# ddr2_memory.net
KiCad netlist of a schematic drawn in Altium Designer
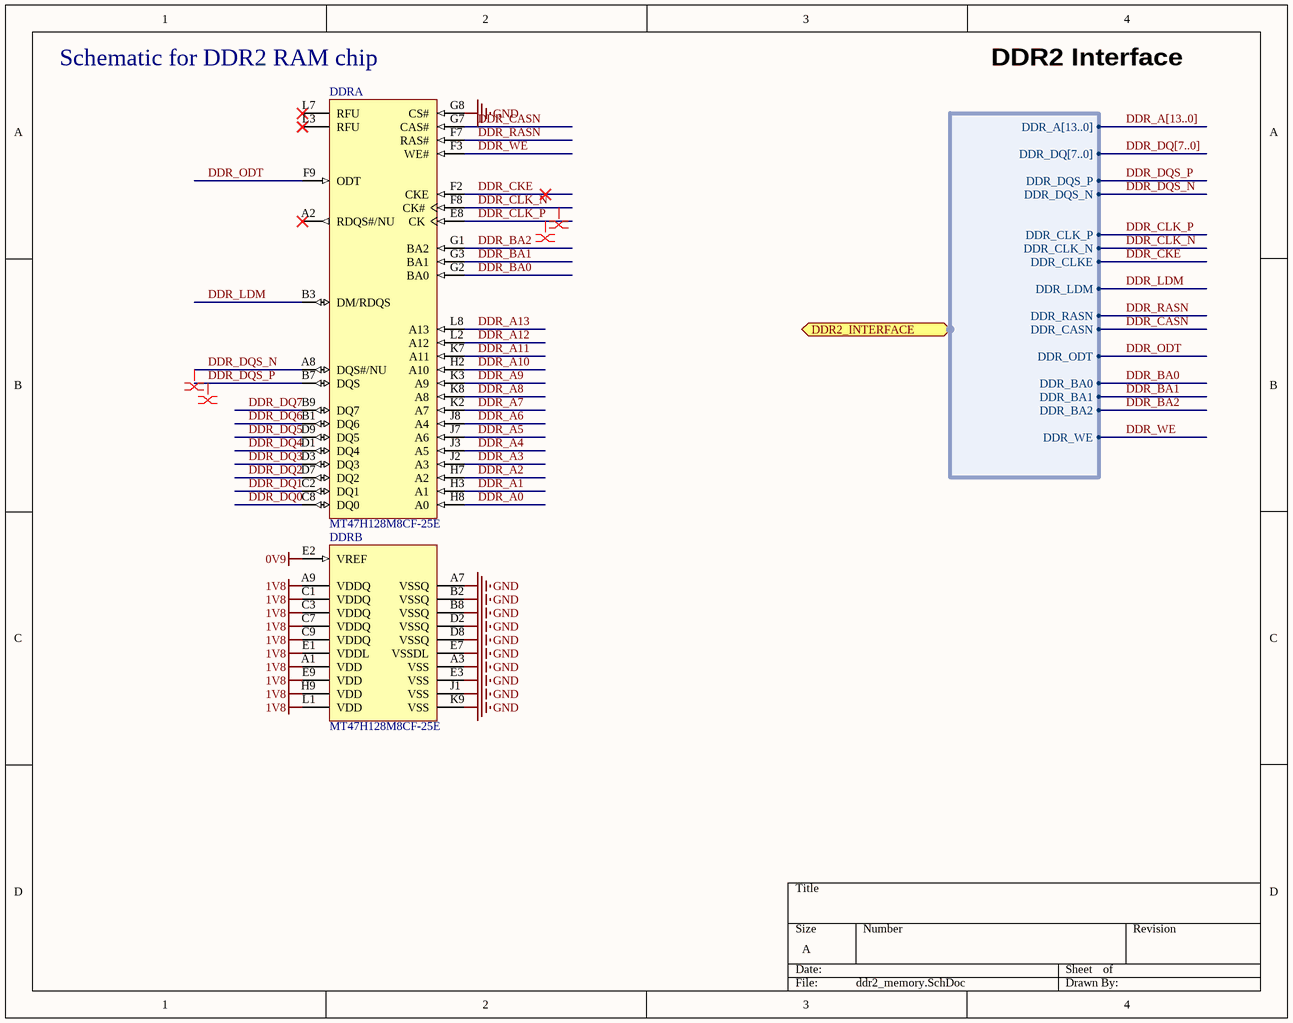
[diagram p0: ddr2_memory.SchDoc]

(export (version "E")
  (design (tool "Eeschema 10.0.6"))
  (components
    (comp (ref "DDR")
      (value "MT47H128M8CF-25E")
      (footprint "MICT-CF-60")
      (description "1Gb DDR2-800 SDRAM, 128Mb x 8, 2.5ns, 1.8V, 0 to 85 degC, 60-Ball FBGA, Pb-Free")
      (fields (field (name "VOLTAGE") "1.8V ") (field (name "MANUFACTURER") "Micron"))
      (libsource (lib "Altium Content Vault") (part "MICT-MT47H128M8CF-60"))
    )
  )
  (nets
    (net (code "3") (name "/DDR_A0") (class "Default")
      (node (ref "DDR") (pin "H8") (pinfunction "A0_H8") (pintype "input"))
    )
    (net (code "4") (name "/DDR_A1") (class "Default")
      (node (ref "DDR") (pin "H3") (pinfunction "A1_H3") (pintype "input"))
    )
    (net (code "5") (name "/DDR_A2") (class "Default")
      (node (ref "DDR") (pin "H7") (pinfunction "A2_H7") (pintype "input"))
    )
    (net (code "6") (name "/DDR_A3") (class "Default")
      (node (ref "DDR") (pin "J2") (pinfunction "A3_J2") (pintype "input"))
    )
    (net (code "7") (name "/DDR_A4") (class "Default")
      (node (ref "DDR") (pin "J3") (pinfunction "A5_J3") (pintype "input"))
    )
    (net (code "8") (name "/DDR_A5") (class "Default")
      (node (ref "DDR") (pin "J7") (pinfunction "A6_J7") (pintype "input"))
    )
    (net (code "9") (name "/DDR_A6") (class "Default")
      (node (ref "DDR") (pin "J8") (pinfunction "A4_J8") (pintype "input"))
    )
    (net (code "10") (name "/DDR_A7") (class "Default")
      (node (ref "DDR") (pin "K2") (pinfunction "A7_K2") (pintype "input"))
    )
    (net (code "11") (name "/DDR_A8") (class "Default")
      (node (ref "DDR") (pin "K8") (pinfunction "A8_K8") (pintype "input"))
    )
    (net (code "12") (name "/DDR_A9") (class "Default")
      (node (ref "DDR") (pin "K3") (pinfunction "A9_K3") (pintype "input"))
    )
    (net (code "13") (name "/DDR_A10") (class "Default")
      (node (ref "DDR") (pin "H2") (pinfunction "A10_H2") (pintype "input"))
    )
    (net (code "14") (name "/DDR_A11") (class "Default")
      (node (ref "DDR") (pin "K7") (pinfunction "A11_K7") (pintype "input"))
    )
    (net (code "15") (name "/DDR_A12") (class "Default")
      (node (ref "DDR") (pin "L2") (pinfunction "A12_L2") (pintype "input"))
    )
    (net (code "16") (name "/DDR_A13") (class "Default")
      (node (ref "DDR") (pin "L8") (pinfunction "A13_L8") (pintype "input"))
    )
    (net (code "18") (name "/DDR_BA0") (class "Default")
      (node (ref "DDR") (pin "G2") (pinfunction "BA0_G2") (pintype "input"))
    )
    (net (code "19") (name "/DDR_BA1") (class "Default")
      (node (ref "DDR") (pin "G3") (pinfunction "BA1_G3") (pintype "input"))
    )
    (net (code "20") (name "/DDR_BA2") (class "Default")
      (node (ref "DDR") (pin "G1") (pinfunction "BA2_G1") (pintype "input"))
    )
    (net (code "21") (name "/DDR_CASN") (class "Default")
      (node (ref "DDR") (pin "G7") (pinfunction "CAS#_G7") (pintype "input"))
    )
    (net (code "22") (name "/DDR_CKE") (class "Default")
      (node (ref "DDR") (pin "F2") (pinfunction "CKE_F2") (pintype "input"))
    )
    (net (code "23") (name "/DDR_CLK_N") (class "Default")
      (node (ref "DDR") (pin "F8") (pinfunction "CK#_F8") (pintype "input"))
    )
    (net (code "24") (name "/DDR_CLK_P") (class "Default")
      (node (ref "DDR") (pin "E8") (pinfunction "CK_E8") (pintype "input"))
    )
    (net (code "25") (name "/DDR_DQ0") (class "Default")
      (node (ref "DDR") (pin "C8") (pinfunction "DQ0_C8") (pintype "bidirectional"))
    )
    (net (code "26") (name "/DDR_DQ1") (class "Default")
      (node (ref "DDR") (pin "C2") (pinfunction "DQ1_C2") (pintype "bidirectional"))
    )
    (net (code "27") (name "/DDR_DQ2") (class "Default")
      (node (ref "DDR") (pin "D7") (pinfunction "DQ2_D7") (pintype "bidirectional"))
    )
    (net (code "28") (name "/DDR_DQ3") (class "Default")
      (node (ref "DDR") (pin "D3") (pinfunction "DQ3_D3") (pintype "bidirectional"))
    )
    (net (code "29") (name "/DDR_DQ4") (class "Default")
      (node (ref "DDR") (pin "D1") (pinfunction "DQ4_D1") (pintype "bidirectional"))
    )
    (net (code "30") (name "/DDR_DQ5") (class "Default")
      (node (ref "DDR") (pin "D9") (pinfunction "DQ5_D9") (pintype "bidirectional"))
    )
    (net (code "31") (name "/DDR_DQ6") (class "Default")
      (node (ref "DDR") (pin "B1") (pinfunction "DQ6_B1") (pintype "bidirectional"))
    )
    (net (code "32") (name "/DDR_DQ7") (class "Default")
      (node (ref "DDR") (pin "B9") (pinfunction "DQ7_B9") (pintype "bidirectional"))
    )
    (net (code "33") (name "/DDR_DQS_N") (class "Default")
      (node (ref "DDR") (pin "A8") (pinfunction "DQS#/NU_A8") (pintype "bidirectional"))
    )
    (net (code "34") (name "/DDR_DQS_P") (class "Default")
      (node (ref "DDR") (pin "B7") (pinfunction "DQS_B7") (pintype "bidirectional"))
    )
    (net (code "35") (name "/DDR_LDM") (class "Default")
      (node (ref "DDR") (pin "B3") (pinfunction "DM/RDQS_B3") (pintype "bidirectional"))
    )
    (net (code "36") (name "/DDR_ODT") (class "Default")
      (node (ref "DDR") (pin "F9") (pinfunction "ODT_F9") (pintype "input"))
    )
    (net (code "37") (name "/DDR_RASN") (class "Default")
      (node (ref "DDR") (pin "F7") (pinfunction "RAS#_F7") (pintype "input"))
    )
    (net (code "38") (name "/DDR_WE") (class "Default")
      (node (ref "DDR") (pin "F3") (pinfunction "WE#_F3") (pintype "input"))
    )
    (net (code "40") (name "0V9") (class "Default")
      (node (ref "DDR") (pin "E2") (pinfunction "VREF_E2") (pintype "input"))
    )
    (net (code "41") (name "1V8") (class "Default")
      (node (ref "DDR") (pin "A1") (pinfunction "VDD_A1") (pintype "power_in"))
      (node (ref "DDR") (pin "A9") (pinfunction "VDDQ_A9") (pintype "power_in"))
      (node (ref "DDR") (pin "C1") (pinfunction "VDDQ_C1") (pintype "power_in"))
      (node (ref "DDR") (pin "C3") (pinfunction "VDDQ_C3") (pintype "power_in"))
      (node (ref "DDR") (pin "C7") (pinfunction "VDDQ_C7") (pintype "power_in"))
      (node (ref "DDR") (pin "C9") (pinfunction "VDDQ_C9") (pintype "power_in"))
      (node (ref "DDR") (pin "E1") (pinfunction "VDDL_E1") (pintype "power_in"))
      (node (ref "DDR") (pin "E9") (pinfunction "VDD_E9") (pintype "power_in"))
      (node (ref "DDR") (pin "H9") (pinfunction "VDD_H9") (pintype "power_in"))
      (node (ref "DDR") (pin "L1") (pinfunction "VDD_L1") (pintype "power_in"))
    )
    (net (code "42") (name "GND") (class "Default")
      (node (ref "DDR") (pin "A3") (pinfunction "VSS_A3") (pintype "power_in"))
      (node (ref "DDR") (pin "A7") (pinfunction "VSSQ_A7") (pintype "power_in"))
      (node (ref "DDR") (pin "B2") (pinfunction "VSSQ_B2") (pintype "power_in"))
      (node (ref "DDR") (pin "B8") (pinfunction "VSSQ_B8") (pintype "power_in"))
      (node (ref "DDR") (pin "D2") (pinfunction "VSSQ_D2") (pintype "power_in"))
      (node (ref "DDR") (pin "D8") (pinfunction "VSSQ_D8") (pintype "power_in"))
      (node (ref "DDR") (pin "E3") (pinfunction "VSS_E3") (pintype "power_in"))
      (node (ref "DDR") (pin "E7") (pinfunction "VSSDL_E7") (pintype "power_in"))
      (node (ref "DDR") (pin "G8") (pinfunction "CS#_G8") (pintype "input"))
      (node (ref "DDR") (pin "J1") (pinfunction "VSS_J1") (pintype "power_in"))
      (node (ref "DDR") (pin "K9") (pinfunction "VSS_K9") (pintype "power_in"))
    )
    (net (code "43") (name "unconnected-(DDRA-RDQS#{slash}NU-PadA2)") (class "Default")
      (node (ref "DDR") (pin "A2") (pinfunction "RDQS#/NU_A2") (pintype "output+no_connect"))
    )
    (net (code "44") (name "unconnected-(DDRA-RFU-PadL3)") (class "Default")
      (node (ref "DDR") (pin "L3") (pinfunction "RFU_L3") (pintype "passive+no_connect"))
    )
    (net (code "45") (name "unconnected-(DDRA-RFU-PadL7)") (class "Default")
      (node (ref "DDR") (pin "L7") (pinfunction "RFU_L7") (pintype "passive+no_connect"))
    )
  )
)
